# pca10184_top_level.net
KiCad netlist of a schematic drawn in Altium Designer
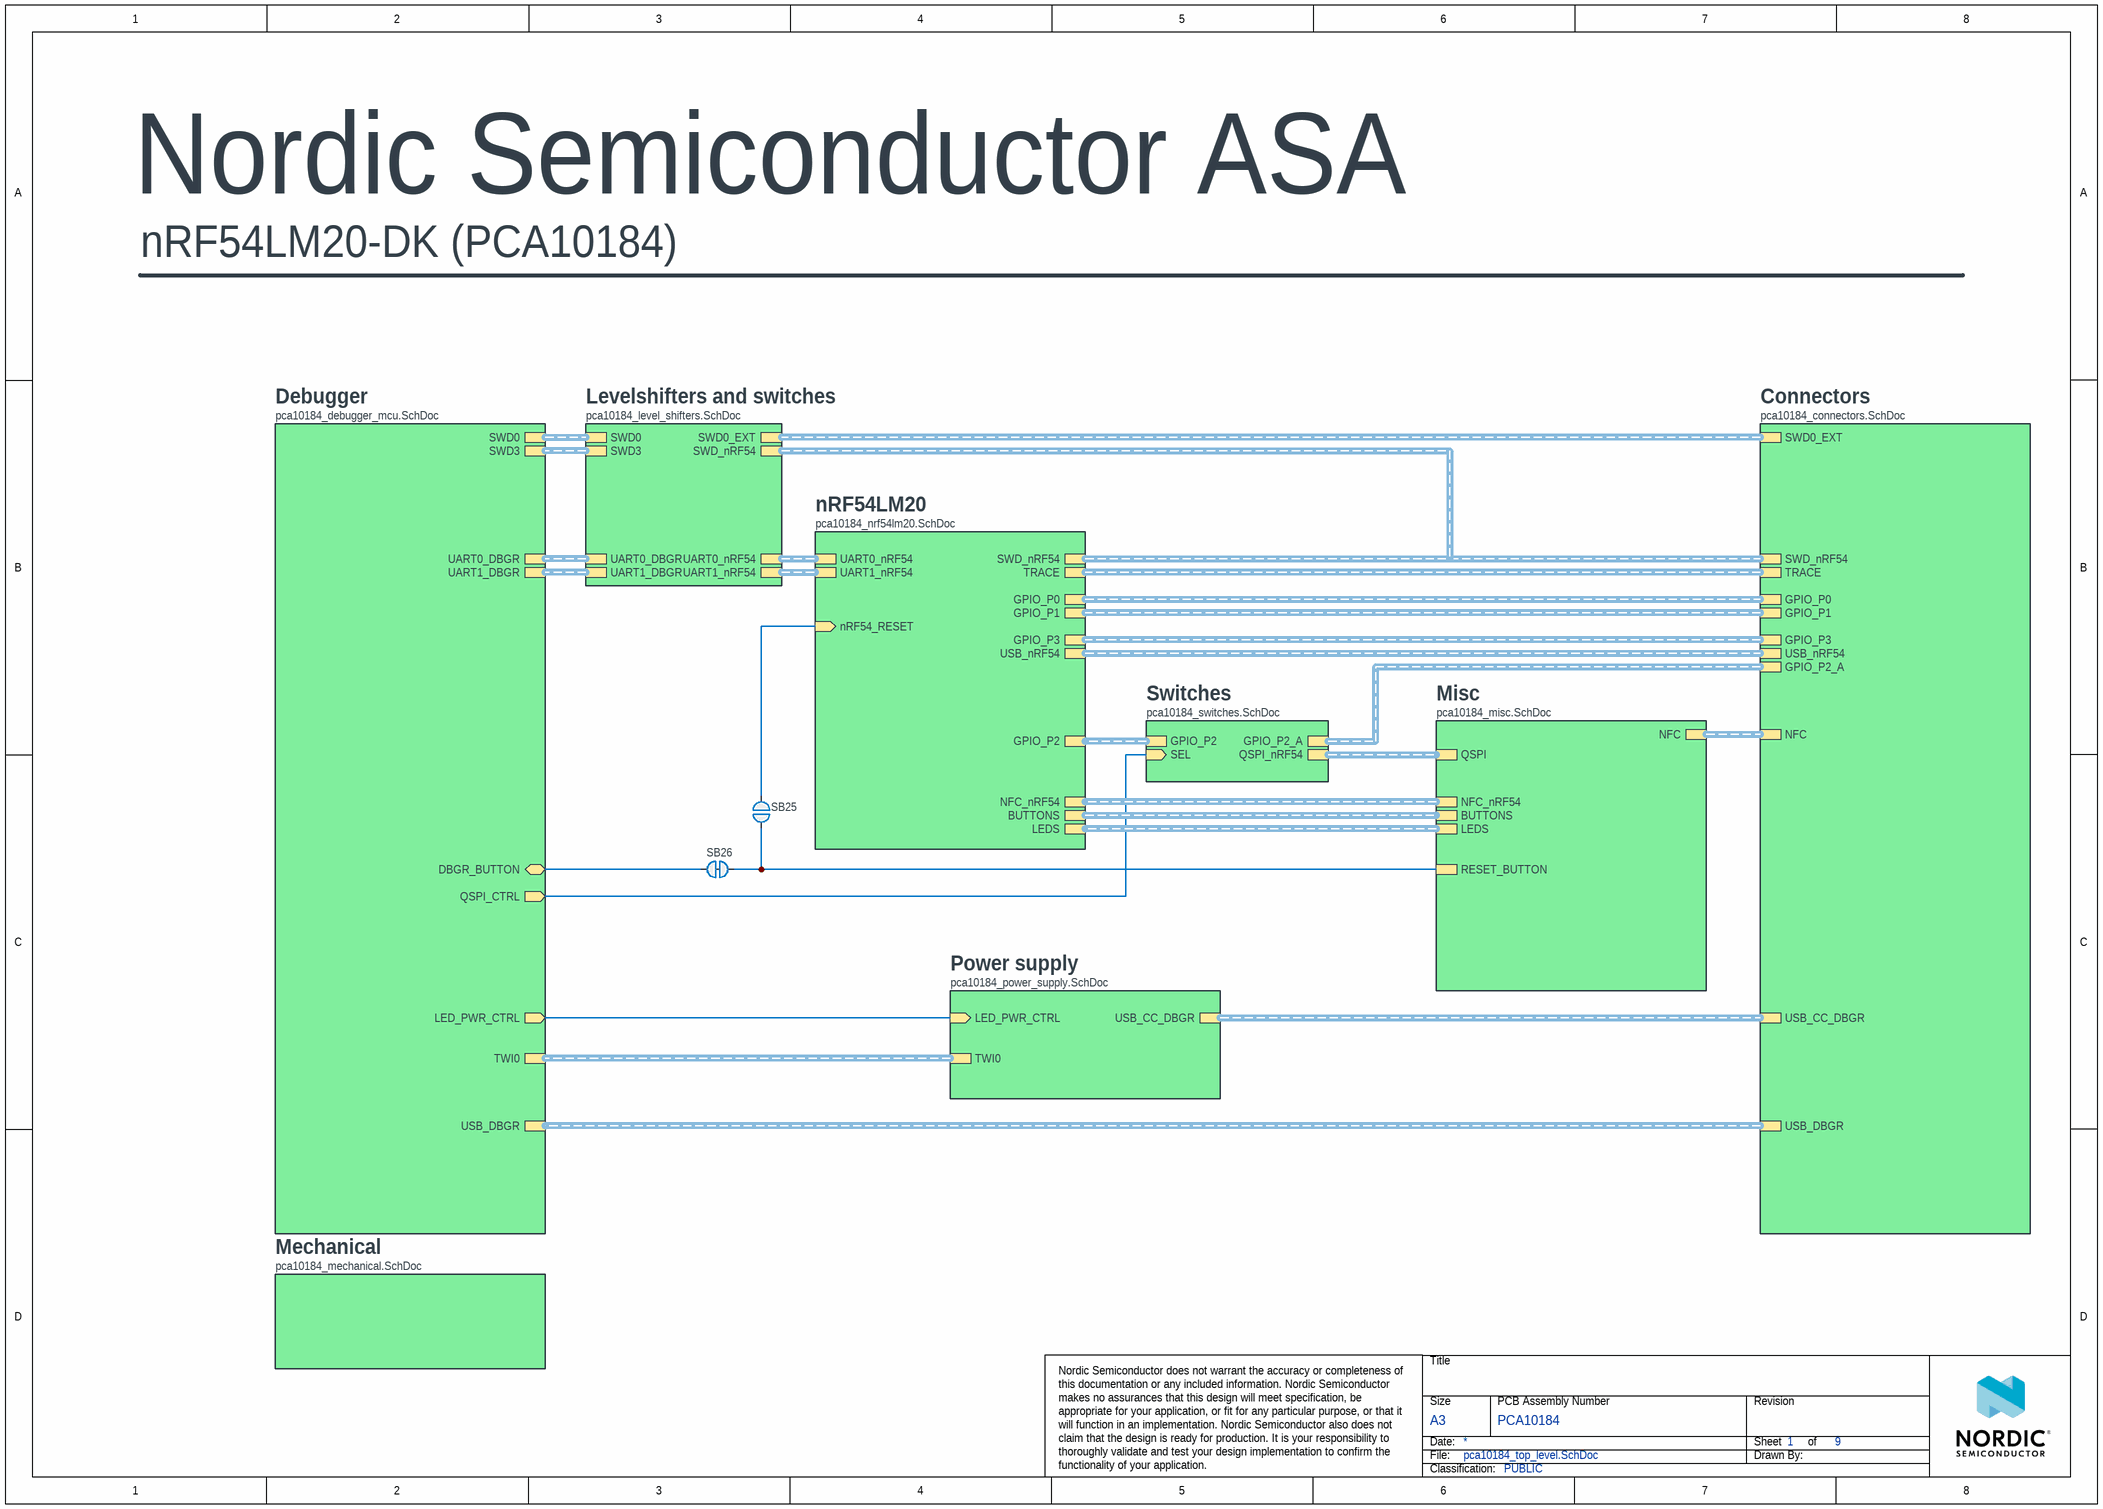
[diagram p0: pca10184_top_level.SchDoc]

(export (version "E")
  (design (tool "Eeschema 10.0.6"))
  (components
    (comp (ref "SB25")
      (value "Solderbridge")
      (footprint "Solderbridge")
      (fields (field (name "MANUFACTURER") "N.A.") (field (name "AUTHOR") "rsk"))
      (libsource (lib "AltiumLib") (part "SOLDERBRIDGE"))
    )
    (comp (ref "SB26")
      (value "Solderbridge")
      (footprint "Solderbridge_Shorted")
      (description "Shorted Solderbridge")
      (fields
        (field (name "PART NUMBER") "Solderbridge Shorted")
        (field (name "MANUFACTURER") "N.A.")
        (field (name "AUTHOR") "rsk")
      )
      (libsource (lib "AltiumLib") (part "SOLDERBRIDGE_SHORTED"))
    )
  )
  (nets
    (net (code "2") (name "/DBGR_BUTTON") (class "Default")
      (node (ref "SB26") (pin "2") (pinfunction "1_2") (pintype "passive"))
    )
    (net (code "14") (name "/RESET_BUTTON") (class "Default")
      (node (ref "SB25") (pin "2") (pinfunction "1_2") (pintype "passive"))
      (node (ref "SB26") (pin "1") (pinfunction "0_1") (pintype "passive"))
    )
    (net (code "28") (name "/nRF54_RESET") (class "Default")
      (node (ref "SB25") (pin "1") (pinfunction "0_1") (pintype "passive"))
    )
  )
)
